# Power_Regulation.net
KiCad netlist of a schematic drawn in Altium Designer
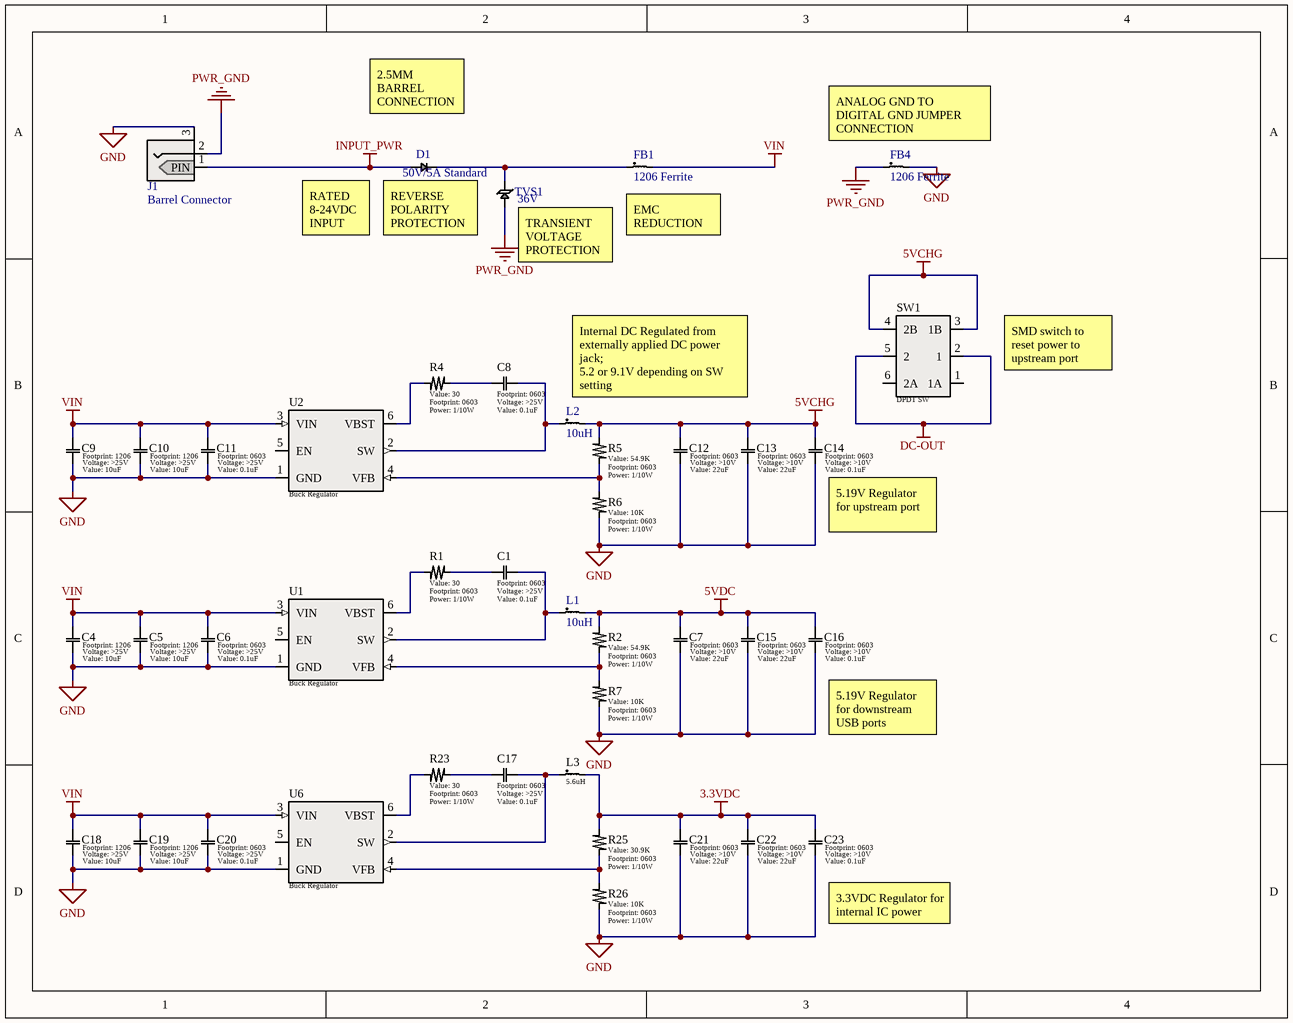
[diagram p0: Power Regulation.SchDoc]

(export (version "E")
  (design (tool "Eeschema 10.0.6"))
  (components
    (comp (ref "C1")
      (value "0.1uF")
      (footprint "0603")
      (fields
        (field (name "VOLTAGE") ">25V")
        (field (name "TOLERANCE") "10%")
        (field (name "Comment") "Generic Capacitor")
      )
      (libsource (lib "Capacitors") (part "Generic Capacitor"))
    )
    (comp (ref "C4")
      (value "10uF")
      (footprint "1206")
      (fields
        (field (name "VOLTAGE") ">25V")
        (field (name "TOLERANCE") "10%")
        (field (name "Comment") "Generic Capacitor")
      )
      (libsource (lib "Capacitors") (part "Generic Capacitor"))
    )
    (comp (ref "C5")
      (value "10uF")
      (footprint "1206")
      (fields
        (field (name "VOLTAGE") ">25V")
        (field (name "TOLERANCE") "10%")
        (field (name "Comment") "Generic Capacitor")
      )
      (libsource (lib "Capacitors") (part "Generic Capacitor"))
    )
    (comp (ref "C6")
      (value "0.1uF")
      (footprint "0603")
      (fields
        (field (name "VOLTAGE") ">25V")
        (field (name "TOLERANCE") "10%")
        (field (name "Comment") "Generic Capacitor")
      )
      (libsource (lib "Capacitors") (part "Generic Capacitor"))
    )
    (comp (ref "C7")
      (value "22uF")
      (footprint "0603")
      (fields
        (field (name "VOLTAGE") ">10V")
        (field (name "TOLERANCE") "20%")
        (field (name "Comment") "Generic Capacitor")
      )
      (libsource (lib "Capacitors") (part "Generic Capacitor"))
    )
    (comp (ref "C8")
      (value "0.1uF")
      (footprint "0603")
      (fields
        (field (name "VOLTAGE") ">25V")
        (field (name "TOLERANCE") "10%")
        (field (name "Comment") "Generic Capacitor")
      )
      (libsource (lib "Capacitors") (part "Generic Capacitor"))
    )
    (comp (ref "C9")
      (value "10uF")
      (footprint "1206")
      (fields
        (field (name "VOLTAGE") ">25V")
        (field (name "TOLERANCE") "10%")
        (field (name "Comment") "Generic Capacitor")
      )
      (libsource (lib "Capacitors") (part "Generic Capacitor"))
    )
    (comp (ref "C10")
      (value "10uF")
      (footprint "1206")
      (fields
        (field (name "VOLTAGE") ">25V")
        (field (name "TOLERANCE") "10%")
        (field (name "Comment") "Generic Capacitor")
      )
      (libsource (lib "Capacitors") (part "Generic Capacitor"))
    )
    (comp (ref "C11")
      (value "0.1uF")
      (footprint "0603")
      (fields
        (field (name "VOLTAGE") ">25V")
        (field (name "TOLERANCE") "10%")
        (field (name "Comment") "Generic Capacitor")
      )
      (libsource (lib "Capacitors") (part "Generic Capacitor"))
    )
    (comp (ref "C12")
      (value "22uF")
      (footprint "0603")
      (fields
        (field (name "VOLTAGE") ">10V")
        (field (name "TOLERANCE") "20%")
        (field (name "Comment") "Generic Capacitor")
      )
      (libsource (lib "Capacitors") (part "Generic Capacitor"))
    )
    (comp (ref "C13")
      (value "22uF")
      (footprint "0603")
      (fields
        (field (name "VOLTAGE") ">10V")
        (field (name "TOLERANCE") "20%")
        (field (name "Comment") "Generic Capacitor")
      )
      (libsource (lib "Capacitors") (part "Generic Capacitor"))
    )
    (comp (ref "C14")
      (value "0.1uF")
      (footprint "0603")
      (fields
        (field (name "VOLTAGE") ">10V")
        (field (name "TOLERANCE") "10%")
        (field (name "Comment") "Generic Capacitor")
      )
      (libsource (lib "Capacitors") (part "Generic Capacitor"))
    )
    (comp (ref "C15")
      (value "22uF")
      (footprint "0603")
      (fields
        (field (name "VOLTAGE") ">10V")
        (field (name "TOLERANCE") "20%")
        (field (name "Comment") "Generic Capacitor")
      )
      (libsource (lib "Capacitors") (part "Generic Capacitor"))
    )
    (comp (ref "C16")
      (value "0.1uF")
      (footprint "0603")
      (fields
        (field (name "VOLTAGE") ">10V")
        (field (name "TOLERANCE") "10%")
        (field (name "Comment") "Generic Capacitor")
      )
      (libsource (lib "Capacitors") (part "Generic Capacitor"))
    )
    (comp (ref "C17")
      (value "0.1uF")
      (footprint "0603")
      (fields
        (field (name "VOLTAGE") ">25V")
        (field (name "TOLERANCE") "10%")
        (field (name "Comment") "Generic Capacitor")
      )
      (libsource (lib "Capacitors") (part "Generic Capacitor"))
    )
    (comp (ref "C18")
      (value "10uF")
      (footprint "1206")
      (fields
        (field (name "VOLTAGE") ">25V")
        (field (name "TOLERANCE") "10%")
        (field (name "Comment") "Generic Capacitor")
      )
      (libsource (lib "Capacitors") (part "Generic Capacitor"))
    )
    (comp (ref "C19")
      (value "10uF")
      (footprint "1206")
      (fields
        (field (name "VOLTAGE") ">25V")
        (field (name "TOLERANCE") "10%")
        (field (name "Comment") "Generic Capacitor")
      )
      (libsource (lib "Capacitors") (part "Generic Capacitor"))
    )
    (comp (ref "C20")
      (value "0.1uF")
      (footprint "0603")
      (fields
        (field (name "VOLTAGE") ">25V")
        (field (name "TOLERANCE") "10%")
        (field (name "Comment") "Generic Capacitor")
      )
      (libsource (lib "Capacitors") (part "Generic Capacitor"))
    )
    (comp (ref "C21")
      (value "22uF")
      (footprint "0603")
      (fields
        (field (name "VOLTAGE") ">10V")
        (field (name "TOLERANCE") "20%")
        (field (name "Comment") "Generic Capacitor")
      )
      (libsource (lib "Capacitors") (part "Generic Capacitor"))
    )
    (comp (ref "C22")
      (value "22uF")
      (footprint "0603")
      (fields
        (field (name "VOLTAGE") ">10V")
        (field (name "TOLERANCE") "20%")
        (field (name "Comment") "Generic Capacitor")
      )
      (libsource (lib "Capacitors") (part "Generic Capacitor"))
    )
    (comp (ref "C23")
      (value "0.1uF")
      (footprint "0603")
      (fields
        (field (name "VOLTAGE") ">10V")
        (field (name "TOLERANCE") "10%")
        (field (name "Comment") "Generic Capacitor")
      )
      (libsource (lib "Capacitors") (part "Generic Capacitor"))
    )
    (comp (ref "D1")
      (value "50V/5A Standard")
      (footprint "DO-214AC")
      (description "Diode Super Barrier 50V 5A Surface Mount")
      (libsource (lib "Diodes") (part "SBRT5A50SA-13"))
    )
    (comp (ref "FB1")
      (value "1206 Ferrite")
      (footprint "1206")
      (description "160 Ohms @ 100MHz 1 Power, Signal Line Ferrite Bead 1206 (3216 Metric) 6A 18mOhm")
      (libsource (lib "Inductors") (part "HI1206T161R-10"))
    )
    (comp (ref "FB4")
      (value "1206 Ferrite")
      (footprint "1206")
      (description "160 Ohms @ 100MHz 1 Power, Signal Line Ferrite Bead 1206 (3216 Metric) 6A 18mOhm")
      (libsource (lib "Inductors") (part "HI1206T161R-10"))
    )
    (comp (ref "J1")
      (value "Barrel Connector")
      (footprint "PJ-082BH")
      (description "CONN PWR JACK 2.5X5.5MM SOLDER")
      (libsource (lib "Connectors") (part "PJ-082BH"))
    )
    (comp (ref "L1")
      (value "10uH")
      (footprint "SMD 8.2x8.6mm")
      (description "5.1A 10uH ±20% 5.2A - Power Inductor")
      (fields
        (field (name "MANUFACTURER_PART_NUMBER") "IHLP3232DZER100M5A")
        (field (name "COPYRIGHT") "Copyright (C) 2023 Ultra Librarian. All rights reserved.")
      )
      (libsource (lib "Inductors") (part "IHLP3232DZER100M5A"))
    )
    (comp (ref "L2")
      (value "10uH")
      (footprint "SMD 8.2x8.6mm")
      (description "5.1A 10uH ±20% 5.2A - Power Inductor")
      (fields
        (field (name "MANUFACTURER_PART_NUMBER") "IHLP3232DZER100M5A")
        (field (name "COPYRIGHT") "Copyright (C) 2023 Ultra Librarian. All rights reserved.")
      )
      (libsource (lib "Inductors") (part "IHLP3232DZER100M5A"))
    )
    (comp (ref "L3")
      (value "5.6uH")
      (footprint "TMPC0402HP")
      (description "2A 5.6uH ±20% SMD Power Inductor")
      (libsource (lib "Inductors") (part "TMPC0402HP-5R6MG-Z02"))
    )
    (comp (ref "R1")
      (value "30")
      (footprint "0603")
      (fields
        (field (name "TOLERANCE") "1%")
        (field (name "POWER") "1/10W")
        (field (name "Comment") "Generic Resistor")
      )
      (libsource (lib "Resistors") (part "Generic Resistor"))
    )
    (comp (ref "R2")
      (value "54.9K")
      (footprint "0603")
      (fields
        (field (name "TOLERANCE") "1%")
        (field (name "POWER") "1/10W")
        (field (name "Comment") "Generic Resistor")
      )
      (libsource (lib "Resistors") (part "Generic Resistor"))
    )
    (comp (ref "R4")
      (value "30")
      (footprint "0603")
      (fields
        (field (name "TOLERANCE") "1%")
        (field (name "POWER") "1/10W")
        (field (name "Comment") "Generic Resistor")
      )
      (libsource (lib "Resistors") (part "Generic Resistor"))
    )
    (comp (ref "R5")
      (value "54.9K")
      (footprint "0603")
      (fields
        (field (name "TOLERANCE") "1%")
        (field (name "POWER") "1/10W")
        (field (name "Comment") "Generic Resistor")
      )
      (libsource (lib "Resistors") (part "Generic Resistor"))
    )
    (comp (ref "R6")
      (value "10K")
      (footprint "0603")
      (fields
        (field (name "TOLERANCE") "1%")
        (field (name "POWER") "1/10W")
        (field (name "Comment") "Generic Resistor")
      )
      (libsource (lib "Resistors") (part "Generic Resistor"))
    )
    (comp (ref "R7")
      (value "10K")
      (footprint "0603")
      (fields
        (field (name "TOLERANCE") "1%")
        (field (name "POWER") "1/10W")
        (field (name "Comment") "Generic Resistor")
      )
      (libsource (lib "Resistors") (part "Generic Resistor"))
    )
    (comp (ref "R23")
      (value "30")
      (footprint "0603")
      (fields
        (field (name "TOLERANCE") "1%")
        (field (name "POWER") "1/10W")
        (field (name "Comment") "Generic Resistor")
      )
      (libsource (lib "Resistors") (part "Generic Resistor"))
    )
    (comp (ref "R25")
      (value "30.9K")
      (footprint "0603")
      (fields
        (field (name "TOLERANCE") "1%")
        (field (name "POWER") "1/10W")
        (field (name "Comment") "Generic Resistor")
      )
      (libsource (lib "Resistors") (part "Generic Resistor"))
    )
    (comp (ref "R26")
      (value "10K")
      (footprint "0603")
      (fields
        (field (name "TOLERANCE") "1%")
        (field (name "POWER") "1/10W")
        (field (name "Comment") "Generic Resistor")
      )
      (libsource (lib "Resistors") (part "Generic Resistor"))
    )
    (comp (ref "SW1")
      (value "DPDT SW")
      (footprint "SMD-DPDT-SW")
      (description "Brick nogging DPDT Black SMD Slide Switch")
      (libsource (lib "Regulators") (part "MS-22D17-G2"))
    )
    (comp (ref "TVS1")
      (value "36V")
      (footprint "DO-214AC")
      (description "58.1V Clamp 6.9A Ipp Tvs Diode Surface Mount DO-214AC (SMA)")
      (libsource (lib "Diodes") (part "SMAJ36A"))
    )
    (comp (ref "U1")
      (value "Buck Regulator")
      (footprint "TSOT-23-6")
      (description "Buck Switching Regulator IC Positive Adjustable 0.8V 1 Output 3A SOT-23-6 Thin, TSOT-23-6")
      (fields
        (field (name "MANUFACTURER") "Texas Instruments")
        (field (name "MANUFACTURER PART NUMBER") "TPS56339DDCR")
      )
      (libsource (lib "Regulators") (part "TPS56339DDCR"))
    )
    (comp (ref "U2")
      (value "Buck Regulator")
      (footprint "TSOT-23-6")
      (description "Buck Switching Regulator IC Positive Adjustable 0.8V 1 Output 3A SOT-23-6 Thin, TSOT-23-6")
      (fields
        (field (name "MANUFACTURER") "Texas Instruments")
        (field (name "MANUFACTURER PART NUMBER") "TPS56339DDCR")
      )
      (libsource (lib "Regulators") (part "TPS56339DDCR"))
    )
    (comp (ref "U6")
      (value "Buck Regulator")
      (footprint "TSOT-23-6")
      (description "Buck Switching Regulator IC Positive Adjustable 0.8V 1 Output 3A SOT-23-6 Thin, TSOT-23-6")
      (fields
        (field (name "MANUFACTURER") "Texas Instruments")
        (field (name "MANUFACTURER PART NUMBER") "TPS56339DDCR")
      )
      (libsource (lib "Regulators") (part "TPS56339DDCR"))
    )
  )
  (nets
    (net (code "1") (name "3.3VDC") (class "Default")
      (node (ref "C21") (pin "1") (pinfunction "1_1") (pintype "passive"))
      (node (ref "C22") (pin "1") (pinfunction "1_1") (pintype "passive"))
      (node (ref "C23") (pin "1") (pinfunction "1_1") (pintype "passive"))
      (node (ref "L3") (pin "2") (pinfunction "2_2") (pintype "passive"))
      (node (ref "R25") (pin "2") (pinfunction "2_2") (pintype "passive"))
    )
    (net (code "2") (name "5VCHG") (class "Default")
      (node (ref "C12") (pin "1") (pinfunction "1_1") (pintype "passive"))
      (node (ref "C13") (pin "1") (pinfunction "1_1") (pintype "passive"))
      (node (ref "C14") (pin "1") (pinfunction "1_1") (pintype "passive"))
      (node (ref "L2") (pin "2") (pinfunction "2_2") (pintype "passive"))
      (node (ref "R5") (pin "2") (pinfunction "2_2") (pintype "passive"))
      (node (ref "SW1") (pin "3") (pinfunction "1B_3") (pintype "passive"))
      (node (ref "SW1") (pin "4") (pinfunction "2B_4") (pintype "passive"))
    )
    (net (code "3") (name "5VDC") (class "Default")
      (node (ref "C15") (pin "1") (pinfunction "1_1") (pintype "passive"))
      (node (ref "C16") (pin "1") (pinfunction "1_1") (pintype "passive"))
      (node (ref "C7") (pin "1") (pinfunction "1_1") (pintype "passive"))
      (node (ref "L1") (pin "2") (pinfunction "2_2") (pintype "passive"))
      (node (ref "R2") (pin "2") (pinfunction "2_2") (pintype "passive"))
    )
    (net (code "4") (name "DC-OUT") (class "Default")
      (node (ref "SW1") (pin "2") (pinfunction "1_2") (pintype "passive"))
      (node (ref "SW1") (pin "5") (pinfunction "2_5") (pintype "passive"))
    )
    (net (code "5") (name "GND") (class "Default")
      (node (ref "C10") (pin "2") (pinfunction "2_2") (pintype "passive"))
      (node (ref "C11") (pin "2") (pinfunction "2_2") (pintype "passive"))
      (node (ref "C12") (pin "2") (pinfunction "2_2") (pintype "passive"))
      (node (ref "C13") (pin "2") (pinfunction "2_2") (pintype "passive"))
      (node (ref "C14") (pin "2") (pinfunction "2_2") (pintype "passive"))
      (node (ref "C15") (pin "2") (pinfunction "2_2") (pintype "passive"))
      (node (ref "C16") (pin "2") (pinfunction "2_2") (pintype "passive"))
      (node (ref "C18") (pin "2") (pinfunction "2_2") (pintype "passive"))
      (node (ref "C19") (pin "2") (pinfunction "2_2") (pintype "passive"))
      (node (ref "C20") (pin "2") (pinfunction "2_2") (pintype "passive"))
      (node (ref "C21") (pin "2") (pinfunction "2_2") (pintype "passive"))
      (node (ref "C22") (pin "2") (pinfunction "2_2") (pintype "passive"))
      (node (ref "C23") (pin "2") (pinfunction "2_2") (pintype "passive"))
      (node (ref "C4") (pin "2") (pinfunction "2_2") (pintype "passive"))
      (node (ref "C5") (pin "2") (pinfunction "2_2") (pintype "passive"))
      (node (ref "C6") (pin "2") (pinfunction "2_2") (pintype "passive"))
      (node (ref "C7") (pin "2") (pinfunction "2_2") (pintype "passive"))
      (node (ref "C9") (pin "2") (pinfunction "2_2") (pintype "passive"))
      (node (ref "FB4") (pin "2") (pinfunction "2_2") (pintype "passive"))
      (node (ref "J1") (pin "3") (pinfunction "SHD_B_3") (pintype "passive"))
      (node (ref "R26") (pin "1") (pinfunction "1_1") (pintype "passive"))
      (node (ref "R6") (pin "1") (pinfunction "1_1") (pintype "passive"))
      (node (ref "R7") (pin "1") (pinfunction "1_1") (pintype "passive"))
      (node (ref "U1") (pin "1") (pinfunction "GND_1") (pintype "passive"))
      (node (ref "U2") (pin "1") (pinfunction "GND_1") (pintype "passive"))
      (node (ref "U6") (pin "1") (pinfunction "GND_1") (pintype "passive"))
    )
    (net (code "6") (name "INPUT_PWR") (class "Default")
      (node (ref "D1") (pin "2") (pinfunction "Anode_2") (pintype "passive"))
      (node (ref "J1") (pin "1") (pinfunction "PIN_1") (pintype "passive"))
    )
    (net (code "7") (name "Net-(C1-Pad1)") (class "Default")
      (node (ref "C1") (pin "1") (pinfunction "1_1") (pintype "passive"))
      (node (ref "R1") (pin "2") (pinfunction "2_2") (pintype "passive"))
    )
    (net (code "8") (name "Net-(C8-Pad1)") (class "Default")
      (node (ref "C8") (pin "1") (pinfunction "1_1") (pintype "passive"))
      (node (ref "R4") (pin "2") (pinfunction "2_2") (pintype "passive"))
    )
    (net (code "9") (name "Net-(C17-Pad1)") (class "Default")
      (node (ref "C17") (pin "1") (pinfunction "1_1") (pintype "passive"))
      (node (ref "R23") (pin "2") (pinfunction "2_2") (pintype "passive"))
    )
    (net (code "10") (name "Net-(D1-Cathode)") (class "Default")
      (node (ref "D1") (pin "1") (pinfunction "Cathode_1") (pintype "passive"))
      (node (ref "FB1") (pin "1") (pinfunction "1_1") (pintype "passive"))
      (node (ref "TVS1") (pin "1") (pinfunction "Cathode_1") (pintype "passive"))
    )
    (net (code "11") (name "Net-(U1-SW)") (class "Default")
      (node (ref "C1") (pin "2") (pinfunction "2_2") (pintype "passive"))
      (node (ref "L1") (pin "1") (pinfunction "1_1") (pintype "passive"))
      (node (ref "U1") (pin "2") (pinfunction "SW_2") (pintype "output"))
    )
    (net (code "12") (name "Net-(U1-VBST)") (class "Default")
      (node (ref "R1") (pin "1") (pinfunction "1_1") (pintype "passive"))
      (node (ref "U1") (pin "6") (pinfunction "VBST_6") (pintype "passive"))
    )
    (net (code "13") (name "Net-(U1-VFB)") (class "Default")
      (node (ref "R2") (pin "1") (pinfunction "1_1") (pintype "passive"))
      (node (ref "R7") (pin "2") (pinfunction "2_2") (pintype "passive"))
      (node (ref "U1") (pin "4") (pinfunction "VFB_4") (pintype "input"))
    )
    (net (code "14") (name "Net-(U2-SW)") (class "Default")
      (node (ref "C8") (pin "2") (pinfunction "2_2") (pintype "passive"))
      (node (ref "L2") (pin "1") (pinfunction "1_1") (pintype "passive"))
      (node (ref "U2") (pin "2") (pinfunction "SW_2") (pintype "output"))
    )
    (net (code "15") (name "Net-(U2-VBST)") (class "Default")
      (node (ref "R4") (pin "1") (pinfunction "1_1") (pintype "passive"))
      (node (ref "U2") (pin "6") (pinfunction "VBST_6") (pintype "passive"))
    )
    (net (code "16") (name "Net-(U2-VFB)") (class "Default")
      (node (ref "R5") (pin "1") (pinfunction "1_1") (pintype "passive"))
      (node (ref "R6") (pin "2") (pinfunction "2_2") (pintype "passive"))
      (node (ref "U2") (pin "4") (pinfunction "VFB_4") (pintype "input"))
    )
    (net (code "17") (name "Net-(U6-SW)") (class "Default")
      (node (ref "C17") (pin "2") (pinfunction "2_2") (pintype "passive"))
      (node (ref "L3") (pin "1") (pinfunction "1_1") (pintype "passive"))
      (node (ref "U6") (pin "2") (pinfunction "SW_2") (pintype "output"))
    )
    (net (code "18") (name "Net-(U6-VBST)") (class "Default")
      (node (ref "R23") (pin "1") (pinfunction "1_1") (pintype "passive"))
      (node (ref "U6") (pin "6") (pinfunction "VBST_6") (pintype "passive"))
    )
    (net (code "19") (name "Net-(U6-VFB)") (class "Default")
      (node (ref "R25") (pin "1") (pinfunction "1_1") (pintype "passive"))
      (node (ref "R26") (pin "2") (pinfunction "2_2") (pintype "passive"))
      (node (ref "U6") (pin "4") (pinfunction "VFB_4") (pintype "input"))
    )
    (net (code "20") (name "PWR_GND") (class "Default")
      (node (ref "FB4") (pin "1") (pinfunction "1_1") (pintype "passive"))
      (node (ref "J1") (pin "2") (pinfunction "SHD_A_2") (pintype "passive"))
      (node (ref "TVS1") (pin "2") (pinfunction "Anode_2") (pintype "passive"))
    )
    (net (code "21") (name "VIN") (class "Default")
      (node (ref "C10") (pin "1") (pinfunction "1_1") (pintype "passive"))
      (node (ref "C11") (pin "1") (pinfunction "1_1") (pintype "passive"))
      (node (ref "C18") (pin "1") (pinfunction "1_1") (pintype "passive"))
      (node (ref "C19") (pin "1") (pinfunction "1_1") (pintype "passive"))
      (node (ref "C20") (pin "1") (pinfunction "1_1") (pintype "passive"))
      (node (ref "C4") (pin "1") (pinfunction "1_1") (pintype "passive"))
      (node (ref "C5") (pin "1") (pinfunction "1_1") (pintype "passive"))
      (node (ref "C6") (pin "1") (pinfunction "1_1") (pintype "passive"))
      (node (ref "C9") (pin "1") (pinfunction "1_1") (pintype "passive"))
      (node (ref "FB1") (pin "2") (pinfunction "2_2") (pintype "passive"))
      (node (ref "U1") (pin "3") (pinfunction "VIN_3") (pintype "input"))
      (node (ref "U2") (pin "3") (pinfunction "VIN_3") (pintype "input"))
      (node (ref "U6") (pin "3") (pinfunction "VIN_3") (pintype "input"))
    )
    (net (code "22") (name "unconnected-(SW1-1A-Pad1)") (class "Default")
      (node (ref "SW1") (pin "1") (pinfunction "1A_1") (pintype "passive"))
    )
    (net (code "23") (name "unconnected-(SW1-2A-Pad6)") (class "Default")
      (node (ref "SW1") (pin "6") (pinfunction "2A_6") (pintype "passive"))
    )
    (net (code "24") (name "unconnected-(U1-EN-Pad5)") (class "Default")
      (node (ref "U1") (pin "5") (pinfunction "EN_5") (pintype "passive"))
    )
    (net (code "25") (name "unconnected-(U2-EN-Pad5)") (class "Default")
      (node (ref "U2") (pin "5") (pinfunction "EN_5") (pintype "passive"))
    )
    (net (code "26") (name "unconnected-(U6-EN-Pad5)") (class "Default")
      (node (ref "U6") (pin "5") (pinfunction "EN_5") (pintype "passive"))
    )
  )
)
